# XTR111_ES.net
KiCad netlist of a schematic drawn in Altium Designer
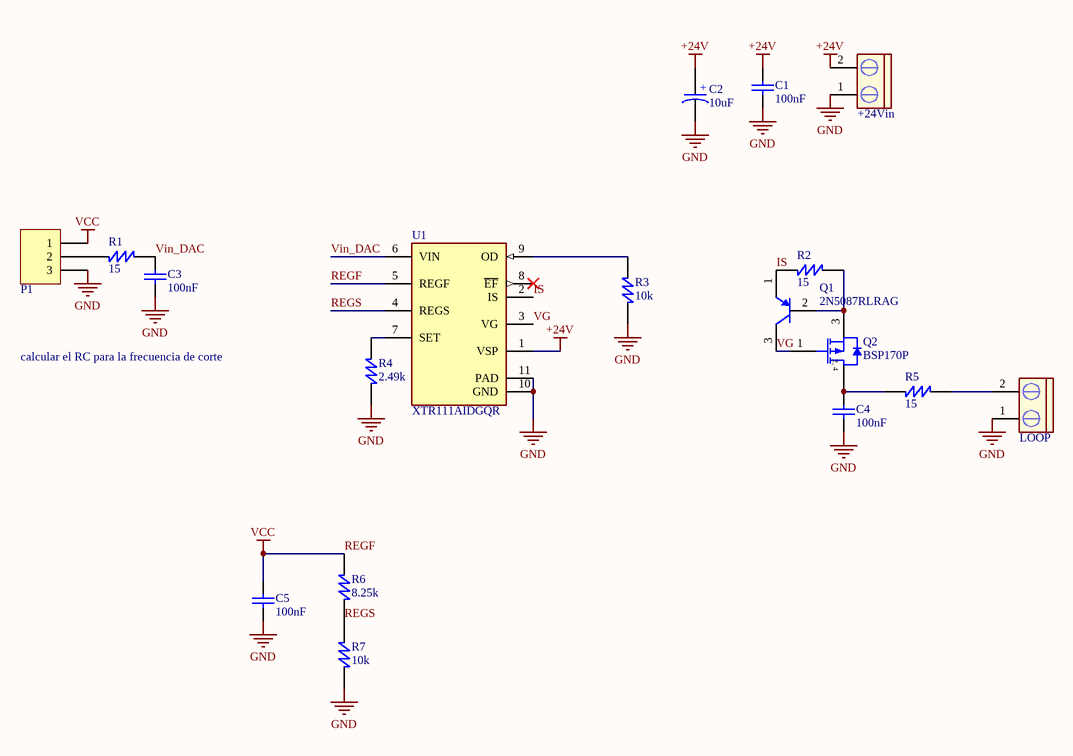
[diagram p0: XTR111_ES.SchDoc]

(export (version "E")
  (design (tool "Eeschema 10.0.6"))
  (components
    (comp (ref "+24Vin")
      (value "CON2 pin blue")
      (footprint "BORNE 2P")
      (description "Connector blue screw")
      (libsource (lib "Libreria3.1") (part "CON2 pin blue"))
    )
    (comp (ref "C1")
      (value "100nF")
      (footprint "CAP 1206")
      (description "CAP-100nf\r\n0402B104K250CT -0603B104K250CT-0805B104K250CT-1206B104K250CT")
      (fields (field (name "PARTNUMBER") "0402B104K250CT"))
      (libsource (lib "Libreria3.1") (part "Cap ceramic"))
    )
    (comp (ref "C2")
      (value "10uF")
      (footprint "CAPRADIAL 6.3X11 - 10u")
      (description "CAP_AXIAL")
      (libsource (lib "Libreria3.1") (part "CAP ELECT"))
    )
    (comp (ref "C3")
      (value "100nF")
      (footprint "CAP 1206")
      (description "CAP-100nf\r\n0402B104K250CT -0603B104K250CT-0805B104K250CT-1206B104K250CT")
      (fields (field (name "PARTNUMBER") "0402B104K250CT"))
      (libsource (lib "Libreria3.1") (part "Cap ceramic"))
    )
    (comp (ref "C4")
      (value "100nF")
      (footprint "CAP 1206")
      (description "CAP-100nf\r\n0402B104K250CT -0603B104K250CT-0805B104K250CT-1206B104K250CT")
      (fields (field (name "PARTNUMBER") "0402B104K250CT"))
      (libsource (lib "Libreria3.1") (part "Cap ceramic"))
    )
    (comp (ref "C5")
      (value "100nF")
      (footprint "CAP 1206")
      (description "CAP-100nf\r\n0402B104K250CT -0603B104K250CT-0805B104K250CT-1206B104K250CT")
      (fields (field (name "PARTNUMBER") "0402B104K250CT"))
      (libsource (lib "Libreria3.1") (part "Cap ceramic"))
    )
    (comp (ref "LOOP")
      (value "CON2 pin blue")
      (footprint "BORNE 2P")
      (description "Connector blue screw")
      (libsource (lib "Libreria3.1") (part "CON2 pin blue"))
    )
    (comp (ref "P1")
      (value "Header 3")
      (footprint "1X03")
      (description "Header, 3-Pin")
      (fields (field (name "PUBLISHER") "Altium Limited"))
      (libsource (lib "Libreria3.1") (part "Header 3"))
    )
    (comp (ref "Q1")
      (value "2N5087RLRAG")
      (footprint "ONSC-TO-92-3-29-11_AM_BL")
      (description "Amplifier Transistor, PNP Silicon, 3-Pin TO-92, Pb-Free, Tape and Reel")
      (fields (field (name "MANUFACTURER") "On Semiconductor"))
      (libsource (lib "Altium Content Vault") (part "ONSC-PNP-E1B2C3-3"))
    )
    (comp (ref "Q2")
      (value "BSP170P")
      (footprint "INF-PG-SOT223_SC-73_N")
      (fields (field (name "MANUFACTURER") "Infineon"))
      (libsource (lib "Altium Content Vault") (part "INF-PEMOS-GDSD-4-A"))
    )
    (comp (ref "R1")
      (value "15")
      (footprint "R1206 Negro")
      (description "resistor")
      (fields (field (name "Comment") "1k"))
      (libsource (lib "Libreria3.1") (part "Res"))
    )
    (comp (ref "R2")
      (value "15")
      (footprint "R1206 Negro")
      (description "resistor")
      (fields (field (name "Comment") "1k"))
      (libsource (lib "Libreria3.1") (part "Res"))
    )
    (comp (ref "R3")
      (value "10k")
      (footprint "R1206 Negro")
      (description "resistor")
      (fields (field (name "Comment") "1k"))
      (libsource (lib "Libreria3.1") (part "Res"))
    )
    (comp (ref "R4")
      (value "2.49k")
      (footprint "R1206 Negro")
      (description "resistor")
      (fields (field (name "Comment") "1k"))
      (libsource (lib "Libreria3.1") (part "Res"))
    )
    (comp (ref "R5")
      (value "15")
      (footprint "R1206 Negro")
      (description "resistor")
      (fields (field (name "Comment") "1k"))
      (libsource (lib "Libreria3.1") (part "Res"))
    )
    (comp (ref "R6")
      (value "8.25k")
      (footprint "R1206 Negro")
      (description "resistor")
      (fields (field (name "Comment") "1k"))
      (libsource (lib "Libreria3.1") (part "Res"))
    )
    (comp (ref "R7")
      (value "10k")
      (footprint "R1206 Negro")
      (description "resistor")
      (fields (field (name "Comment") "1k"))
      (libsource (lib "Libreria3.1") (part "Res"))
    )
    (comp (ref "U1")
      (value "XTR111AIDGQR")
      (footprint "FP-DGQ0010D-MFG")
      (description "IC PREC VOLT-CURR CONV/TX 10MSOP")
      (fields
        (field (name "MANUFACTURER") "Texas Instruments")
        (field (name "OCTOPART") "https://octopart.com/xtr111aidgqr-texas+instruments-7116478")
      )
      (libsource (lib "Altium Content Vault") (part "9494b115a78206cd056ed6728263eda"))
    )
  )
  (nets
    (net (code "1") (name "+24V") (class "Default")
      (node (ref "+24Vin") (pin "2") (pinfunction "2_2") (pintype "passive"))
      (node (ref "C1") (pin "2") (pinfunction "2_2") (pintype "passive"))
      (node (ref "C2") (pin "1") (pinfunction "1_1") (pintype "passive"))
      (node (ref "U1") (pin "1") (pinfunction "VSP_1") (pintype "power_in"))
    )
    (net (code "2") (name "/IS") (class "Default")
      (node (ref "Q1") (pin "1") (pinfunction "E_1") (pintype "passive"))
      (node (ref "R2") (pin "2") (pinfunction "2_2") (pintype "passive"))
      (node (ref "U1") (pin "2") (pinfunction "IS_2") (pintype "passive"))
    )
    (net (code "3") (name "/REGS") (class "Default")
      (node (ref "R6") (pin "1") (pinfunction "1_1") (pintype "passive"))
      (node (ref "R7") (pin "2") (pinfunction "2_2") (pintype "passive"))
      (node (ref "U1") (pin "4") (pinfunction "REGS_4") (pintype "passive"))
    )
    (net (code "4") (name "/VG") (class "Default")
      (node (ref "Q1") (pin "3") (pinfunction "C_3") (pintype "passive"))
      (node (ref "Q2") (pin "1") (pinfunction "GATE_1") (pintype "passive"))
      (node (ref "U1") (pin "3") (pinfunction "VG_3") (pintype "passive"))
    )
    (net (code "5") (name "/Vin_DAC") (class "Default")
      (node (ref "C3") (pin "2") (pinfunction "2_2") (pintype "passive"))
      (node (ref "R1") (pin "1") (pinfunction "1_1") (pintype "passive"))
      (node (ref "U1") (pin "6") (pinfunction "VIN_6") (pintype "power_in"))
    )
    (net (code "6") (name "GND") (class "Default")
      (node (ref "+24Vin") (pin "1") (pinfunction "1_1") (pintype "passive"))
      (node (ref "C1") (pin "1") (pinfunction "1_1") (pintype "passive"))
      (node (ref "C2") (pin "2") (pinfunction "2_2") (pintype "passive"))
      (node (ref "C3") (pin "1") (pinfunction "1_1") (pintype "passive"))
      (node (ref "C4") (pin "1") (pinfunction "1_1") (pintype "passive"))
      (node (ref "C5") (pin "1") (pinfunction "1_1") (pintype "passive"))
      (node (ref "LOOP") (pin "1") (pinfunction "1_1") (pintype "passive"))
      (node (ref "P1") (pin "3") (pinfunction "3_3") (pintype "passive"))
      (node (ref "R3") (pin "1") (pinfunction "1_1") (pintype "passive"))
      (node (ref "R4") (pin "1") (pinfunction "1_1") (pintype "passive"))
      (node (ref "R7") (pin "1") (pinfunction "1_1") (pintype "passive"))
      (node (ref "U1") (pin "10") (pinfunction "GND_10") (pintype "power_in"))
      (node (ref "U1") (pin "11") (pinfunction "PAD_11") (pintype "power_in"))
    )
    (net (code "7") (name "Net-(C4-Pad2)") (class "Default")
      (node (ref "C4") (pin "2") (pinfunction "2_2") (pintype "passive"))
      (node (ref "Q2") (pin "2") (pinfunction "DRAIN_2") (pintype "passive"))
      (node (ref "Q2") (pin "4") (pinfunction "DRAIN_4") (pintype "passive"))
      (node (ref "R5") (pin "2") (pinfunction "2_2") (pintype "passive"))
    )
    (net (code "8") (name "Net-(LOOP-Pad2)") (class "Default")
      (node (ref "LOOP") (pin "2") (pinfunction "2_2") (pintype "passive"))
      (node (ref "R5") (pin "1") (pinfunction "1_1") (pintype "passive"))
    )
    (net (code "9") (name "Net-(P1-Pad2)") (class "Default")
      (node (ref "P1") (pin "2") (pinfunction "2_2") (pintype "passive"))
      (node (ref "R1") (pin "2") (pinfunction "2_2") (pintype "passive"))
    )
    (net (code "10") (name "Net-(Q1-B)") (class "Default")
      (node (ref "Q1") (pin "2") (pinfunction "B_2") (pintype "passive"))
      (node (ref "Q2") (pin "3") (pinfunction "SOURCE_3") (pintype "passive"))
      (node (ref "R2") (pin "1") (pinfunction "1_1") (pintype "passive"))
    )
    (net (code "11") (name "Net-(U1-OD)") (class "Default")
      (node (ref "R3") (pin "2") (pinfunction "2_2") (pintype "passive"))
      (node (ref "U1") (pin "9") (pinfunction "OD_9") (pintype "input"))
    )
    (net (code "12") (name "Net-(U1-SET)") (class "Default")
      (node (ref "R4") (pin "2") (pinfunction "2_2") (pintype "passive"))
      (node (ref "U1") (pin "7") (pinfunction "SET_7") (pintype "passive"))
    )
    (net (code "13") (name "VCC") (class "Default")
      (node (ref "C5") (pin "2") (pinfunction "2_2") (pintype "passive"))
      (node (ref "P1") (pin "1") (pinfunction "1_1") (pintype "passive"))
      (node (ref "R6") (pin "2") (pinfunction "2_2") (pintype "passive"))
      (node (ref "U1") (pin "5") (pinfunction "REGF_5") (pintype "passive"))
    )
    (net (code "14") (name "unconnected-(U1-~{EF}-Pad8)") (class "Default")
      (node (ref "U1") (pin "8") (pinfunction "~{EF}_8") (pintype "output+no_connect"))
    )
  )
)
